# Etapa_Regulacion.net
KiCad netlist of a schematic drawn in Altium Designer
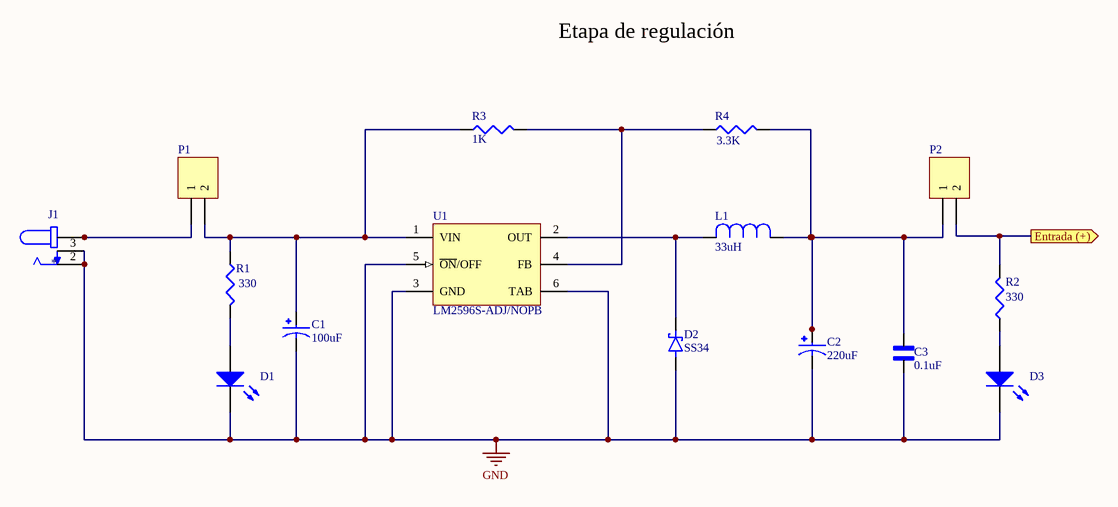
[diagram p0: Etapa_Regulacion.SchDoc]

(export (version "E")
  (design (tool "Eeschema 10.0.6"))
  (components
    (comp (ref "C1")
      (value "100uF")
      (footprint "CAP_16SVPG220M")
      (fields (field (name "MP") "16SVPG220M"))
      (libsource (lib "CAP_220uF") (part "16SVPG220M"))
    )
    (comp (ref "C2")
      (value "220uF")
      (footprint "CAP_16SVPG220M")
      (fields (field (name "MP") "16SVPG220M"))
      (libsource (lib "CAP_220uF") (part "16SVPG220M"))
    )
    (comp (ref "C3")
      (value "0.1uF")
      (footprint "CAPC4632X221N")
      (fields (field (name "MP") "1812CC104KAZ1A"))
      (libsource (lib "CAP_01uf") (part "1812CC104KAZ1A"))
    )
    (comp (ref "D1")
      (value "LED2")
      (footprint "3.2X1.6X1.1")
      (description "Typical RED, GREEN, YELLOW, AMBER GaAs LED")
      (fields (field (name "PUBLISHER") "Altium Limited"))
      (libsource (lib "Miscellaneous Devices") (part "LED2"))
    )
    (comp (ref "D2")
      (value "SS34")
      (footprint "DIOM7959X265N")
      (description "Diode Schottky 40V 3A Surface Mount SMC _DO-214AB_")
      (fields (field (name "MF") "ON Semiconductor"))
      (libsource (lib "SS34") (part "SS34"))
    )
    (comp (ref "D3")
      (value "LED2")
      (footprint "3.2X1.6X1.1")
      (description "Typical RED, GREEN, YELLOW, AMBER GaAs LED")
      (fields (field (name "PUBLISHER") "Altium Limited"))
      (libsource (lib "Miscellaneous Devices") (part "LED2"))
    )
    (comp (ref "J1")
      (value "*")
      (footprint "CUI_PJ-002BH-SMT-TR")
      (description "2.5 x 6.5 mm, 5.0 A, Horizontal, Surface Mount _SMT_, Dc Power Jack Connector")
      (fields (field (name "MF") "CUI Devices") (field (name "MP") "PJ-002BH-SMT-TR"))
      (libsource (lib "*") (part "PJ-002BH-SMT-TR"))
    )
    (comp (ref "L1")
      (value "33uH")
      (footprint "IND_CDRH127/LDNP-470MC_SUM")
      (description "47ÂµH Shielded Inductor 3.25A 78mOhm Max Nonstandard")
      (fields (field (name "DIGI-KEY_PART_NUMBER") "308-1339-1-ND") (field (name "MF") "Sumida America"))
      (libsource (lib "IND_L1") (part "CDRH127/LDNP-470MC"))
    )
    (comp (ref "P1")
      (value "Header 2")
      (footprint "HDR1X2")
      (description "Header, 2-Pin")
      (fields (field (name "PUBLISHER") "Altium Limited"))
      (libsource (lib "Miscellaneous Connectors") (part "Header 2"))
    )
    (comp (ref "P2")
      (value "Header 2")
      (footprint "HDR1X2")
      (description "Header, 2-Pin")
      (fields (field (name "PUBLISHER") "Altium Limited"))
      (libsource (lib "Miscellaneous Connectors") (part "Header 2"))
    )
    (comp (ref "R1")
      (value "330")
      (footprint "J1-0805")
      (description "Resistor")
      (fields (field (name "Comment") "Res3") (field (name "PUBLISHER") "Altium Limited"))
      (libsource (lib "Miscellaneous Devices") (part "Res3"))
    )
    (comp (ref "R2")
      (value "330")
      (footprint "J1-0805")
      (description "Resistor")
      (fields (field (name "Comment") "Res3") (field (name "PUBLISHER") "Altium Limited"))
      (libsource (lib "Miscellaneous Devices") (part "Res3"))
    )
    (comp (ref "R3")
      (value "1K")
      (footprint "J1-0805")
      (description "Resistor")
      (fields (field (name "Comment") "Res3") (field (name "PUBLISHER") "Altium Limited"))
      (libsource (lib "Miscellaneous Devices") (part "Res3"))
    )
    (comp (ref "R4")
      (value "3.3K")
      (footprint "J1-0805")
      (description "Resistor")
      (fields (field (name "Comment") "Res3") (field (name "PUBLISHER") "Altium Limited"))
      (libsource (lib "Miscellaneous Devices") (part "Res3"))
    )
    (comp (ref "U1")
      (value "LM2596S-ADJ/NOPB")
      (footprint "KTT0005B_N")
      (description "SIMPLE SWITCHER® Power Converter 150 KHz 3A Step-Down Voltage Regulator, 5-pin TO-263, Pb-Free")
      (fields (field (name "MANUFACTURER") "Texas Instruments"))
      (libsource (lib "Regulador") (part "CMP-0069-00271-3"))
    )
  )
  (nets
    (net (code "1") (name "/Entrada (+)") (class "Default")
      (node (ref "P2") (pin "2") (pinfunction "2_2") (pintype "passive"))
      (node (ref "R2") (pin "2") (pinfunction "2_2") (pintype "passive"))
    )
    (net (code "2") (name "GND") (class "Default")
      (node (ref "C1") (pin "2") (pinfunction "2_2") (pintype "passive"))
      (node (ref "C2") (pin "2") (pinfunction "2_2") (pintype "passive"))
      (node (ref "C3") (pin "1") (pinfunction "1_1") (pintype "passive"))
      (node (ref "D1") (pin "2") (pinfunction "K_2") (pintype "passive"))
      (node (ref "D2") (pin "1") (pinfunction "A_1") (pintype "passive"))
      (node (ref "D3") (pin "2") (pinfunction "K_2") (pintype "passive"))
      (node (ref "J1") (pin "2") (pinfunction "2_2") (pintype "passive"))
      (node (ref "J1") (pin "3") (pinfunction "3_3") (pintype "passive"))
      (node (ref "U1") (pin "3") (pinfunction "GND_3") (pintype "power_in"))
      (node (ref "U1") (pin "5") (pinfunction "~{ON}/OFF_5") (pintype "input"))
      (node (ref "U1") (pin "6") (pinfunction "TAB_6") (pintype "power_in"))
    )
    (net (code "3") (name "Net-(C2-Pad1)") (class "Default")
      (node (ref "C2") (pin "1") (pinfunction "1_1") (pintype "passive"))
      (node (ref "C3") (pin "2") (pinfunction "2_2") (pintype "passive"))
      (node (ref "L1") (pin "1") (pinfunction "1_1") (pintype "passive"))
      (node (ref "P2") (pin "1") (pinfunction "1_1") (pintype "passive"))
      (node (ref "R4") (pin "2") (pinfunction "2_2") (pintype "passive"))
    )
    (net (code "4") (name "Net-(D1-A)") (class "Default")
      (node (ref "D1") (pin "1") (pinfunction "A_1") (pintype "passive"))
      (node (ref "R1") (pin "2") (pinfunction "2_2") (pintype "passive"))
    )
    (net (code "5") (name "Net-(D2-K)") (class "Default")
      (node (ref "D2") (pin "2") (pinfunction "K_2") (pintype "passive"))
      (node (ref "L1") (pin "2") (pinfunction "2_2") (pintype "passive"))
      (node (ref "U1") (pin "2") (pinfunction "OUT_2") (pintype "power_in"))
    )
    (net (code "6") (name "Net-(D3-A)") (class "Default")
      (node (ref "D3") (pin "1") (pinfunction "A_1") (pintype "passive"))
      (node (ref "R2") (pin "1") (pinfunction "1_1") (pintype "passive"))
    )
    (net (code "7") (name "Net-(J1-1-Pad1A)") (class "Default")
      (node (ref "J1") (pin "1A") (pinfunction "1_1A") (pintype "passive"))
      (node (ref "J1") (pin "1B") (pinfunction "1_1B") (pintype "passive"))
      (node (ref "P1") (pin "1") (pinfunction "1_1") (pintype "passive"))
    )
    (net (code "8") (name "Net-(U1-FB)") (class "Default")
      (node (ref "R3") (pin "2") (pinfunction "2_2") (pintype "passive"))
      (node (ref "R4") (pin "1") (pinfunction "1_1") (pintype "passive"))
      (node (ref "U1") (pin "4") (pinfunction "FB_4") (pintype "passive"))
    )
    (net (code "9") (name "Net-(U1-VIN)") (class "Default")
      (node (ref "C1") (pin "1") (pinfunction "1_1") (pintype "passive"))
      (node (ref "P1") (pin "2") (pinfunction "2_2") (pintype "passive"))
      (node (ref "R1") (pin "1") (pinfunction "1_1") (pintype "passive"))
      (node (ref "R3") (pin "1") (pinfunction "1_1") (pintype "passive"))
      (node (ref "U1") (pin "1") (pinfunction "VIN_1") (pintype "power_in"))
    )
  )
)
